# ICE.net
KiCad netlist of a schematic drawn in Altium Designer
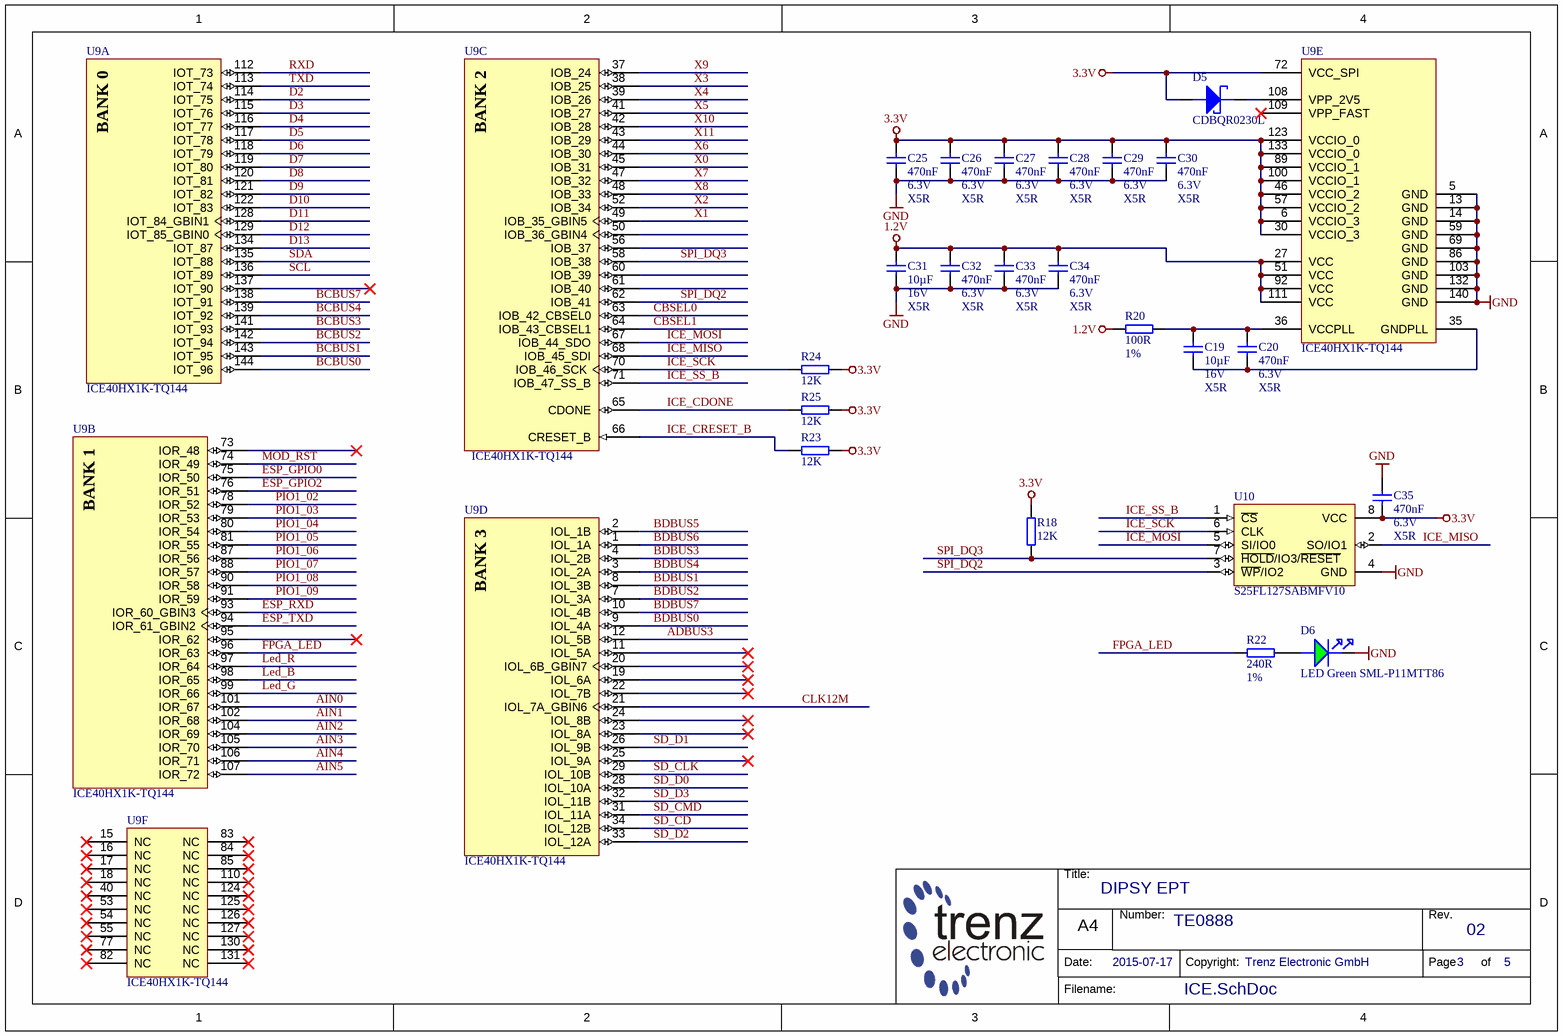
[diagram p0: ICE.SchDoc]

(export (version "E")
  (design (tool "Eeschema 10.0.6"))
  (components
    (comp (ref "C19")
      (value "10µF")
      (footprint "CAPC1608X90N")
      (description "KON 10µF 16V X5R SMD 20%")
      (fields
        (field (name "VOLTAGE") "16V")
        (field (name "TECHNOLOGY") "X5R")
        (field (name "TOLERANCE") "20%")
      )
      (libsource (lib "TE") (part "CAP-NP"))
    )
    (comp (ref "C20")
      (value "470nF")
      (footprint "CAPC0603X33N")
      (description "KON 470nF X5R 6.3V SMD 20%")
      (fields
        (field (name "VOLTAGE") "6.3V")
        (field (name "TECHNOLOGY") "X5R")
        (field (name "TOLERANCE") "20%")
      )
      (libsource (lib "TE") (part "CAP-NP"))
    )
    (comp (ref "C25")
      (value "470nF")
      (footprint "CAPC0603X33N")
      (description "KON 470nF X5R 6.3V SMD 20%")
      (fields
        (field (name "VOLTAGE") "6.3V")
        (field (name "TECHNOLOGY") "X5R")
        (field (name "TOLERANCE") "20%")
      )
      (libsource (lib "TE") (part "CAP-NP"))
    )
    (comp (ref "C26")
      (value "470nF")
      (footprint "CAPC0603X33N")
      (description "KON 470nF X5R 6.3V SMD 20%")
      (fields
        (field (name "VOLTAGE") "6.3V")
        (field (name "TECHNOLOGY") "X5R")
        (field (name "TOLERANCE") "20%")
      )
      (libsource (lib "TE") (part "CAP-NP"))
    )
    (comp (ref "C27")
      (value "470nF")
      (footprint "CAPC0603X33N")
      (description "KON 470nF X5R 6.3V SMD 20%")
      (fields
        (field (name "VOLTAGE") "6.3V")
        (field (name "TECHNOLOGY") "X5R")
        (field (name "TOLERANCE") "20%")
      )
      (libsource (lib "TE") (part "CAP-NP"))
    )
    (comp (ref "C28")
      (value "470nF")
      (footprint "CAPC0603X33N")
      (description "KON 470nF X5R 6.3V SMD 20%")
      (fields
        (field (name "VOLTAGE") "6.3V")
        (field (name "TECHNOLOGY") "X5R")
        (field (name "TOLERANCE") "20%")
      )
      (libsource (lib "TE") (part "CAP-NP"))
    )
    (comp (ref "C29")
      (value "470nF")
      (footprint "CAPC0603X33N")
      (description "KON 470nF X5R 6.3V SMD 20%")
      (fields
        (field (name "VOLTAGE") "6.3V")
        (field (name "TECHNOLOGY") "X5R")
        (field (name "TOLERANCE") "20%")
      )
      (libsource (lib "TE") (part "CAP-NP"))
    )
    (comp (ref "C30")
      (value "470nF")
      (footprint "CAPC0603X33N")
      (description "KON 470nF X5R 6.3V SMD 20%")
      (fields
        (field (name "VOLTAGE") "6.3V")
        (field (name "TECHNOLOGY") "X5R")
        (field (name "TOLERANCE") "20%")
      )
      (libsource (lib "TE") (part "CAP-NP"))
    )
    (comp (ref "C31")
      (value "10µF")
      (footprint "CAPC1608X90N")
      (description "KON 10µF 16V X5R SMD 20%")
      (fields
        (field (name "VOLTAGE") "16V")
        (field (name "TECHNOLOGY") "X5R")
        (field (name "TOLERANCE") "20%")
      )
      (libsource (lib "TE") (part "CAP-NP"))
    )
    (comp (ref "C32")
      (value "470nF")
      (footprint "CAPC0603X33N")
      (description "KON 470nF X5R 6.3V SMD 20%")
      (fields
        (field (name "VOLTAGE") "6.3V")
        (field (name "TECHNOLOGY") "X5R")
        (field (name "TOLERANCE") "20%")
      )
      (libsource (lib "TE") (part "CAP-NP"))
    )
    (comp (ref "C33")
      (value "470nF")
      (footprint "CAPC0603X33N")
      (description "KON 470nF X5R 6.3V SMD 20%")
      (fields
        (field (name "VOLTAGE") "6.3V")
        (field (name "TECHNOLOGY") "X5R")
        (field (name "TOLERANCE") "20%")
      )
      (libsource (lib "TE") (part "CAP-NP"))
    )
    (comp (ref "C34")
      (value "470nF")
      (footprint "CAPC0603X33N")
      (description "KON 470nF X5R 6.3V SMD 20%")
      (fields
        (field (name "VOLTAGE") "6.3V")
        (field (name "TECHNOLOGY") "X5R")
        (field (name "TOLERANCE") "20%")
      )
      (libsource (lib "TE") (part "CAP-NP"))
    )
    (comp (ref "C35")
      (value "470nF")
      (footprint "CAPC0603X33N")
      (description "KON 470nF X5R 6.3V SMD 20%")
      (fields
        (field (name "VOLTAGE") "6.3V")
        (field (name "TECHNOLOGY") "X5R")
        (field (name "TOLERANCE") "20%")
      )
      (libsource (lib "TE") (part "CAP-NP"))
    )
    (comp (ref "D5")
      (value "CDBQR0230L")
      (footprint "DIOC1006X55N")
      (fields (field (name "VOLTAGE") "0.2A"))
      (libsource (lib "TE") (part "SCHOTTKY"))
    )
    (comp (ref "D6")
      (value "LED Green SML-P11MTT86")
      (footprint "LEDC1006X25N_GREEN")
      (description "LED Grün SML-P11MTT86 SMD")
      (libsource (lib "TE") (part "LED_GRUEN"))
    )
    (comp (ref "R18")
      (value "12K")
      (footprint "RESC1005X40N")
      (description "WID SMD 12K 1% 0,063W")
      (libsource (lib "TE") (part "RES"))
    )
    (comp (ref "R20")
      (value "100R")
      (footprint "RESC1005X40N")
      (description "WID SMD 100R 1% 0,063W")
      (fields (field (name "TOLERANCE") "1%"))
      (libsource (lib "TE") (part "RES"))
    )
    (comp (ref "R22")
      (value "240R")
      (footprint "RESC1005X40N")
      (description "WID SMD 240R 1% 0,063W")
      (fields (field (name "TOLERANCE") "1%"))
      (libsource (lib "TE") (part "RES"))
    )
    (comp (ref "R23")
      (value "12K")
      (footprint "RESC1005X40N")
      (description "WID SMD 12K 1% 0,063W")
      (libsource (lib "TE") (part "RES"))
    )
    (comp (ref "R24")
      (value "12K")
      (footprint "RESC1005X40N")
      (description "WID SMD 12K 1% 0,063W")
      (libsource (lib "TE") (part "RES"))
    )
    (comp (ref "R25")
      (value "12K")
      (footprint "RESC1005X40N")
      (description "WID SMD 12K 1% 0,063W")
      (libsource (lib "TE") (part "RES"))
    )
    (comp (ref "U9")
      (value "ICE40HX1K-TQ144")
      (footprint "QFP50P2200X2200X160-144N")
      (libsource (lib "TE") (part "ICE40HX1K-TQ144"))
    )
    (comp (ref "U10")
      (value "S25FL127SABMFV10")
      (footprint "SOIC127P790X216-8N")
      (description "S25FL127SABMFV10 automotive SO8")
      (libsource (lib "TE") (part "S25FL127S-SO8"))
    )
  )
  (nets
    (net (code "1") (name "/ADBUS3") (class "Default")
      (node (ref "U9") (pin "12") (pinfunction "IOL_5B_12") (pintype "bidirectional"))
    )
    (net (code "2") (name "/AIN0") (class "Default")
      (node (ref "U9") (pin "101") (pinfunction "IOR_67_101") (pintype "bidirectional"))
    )
    (net (code "3") (name "/AIN1") (class "Default")
      (node (ref "U9") (pin "102") (pinfunction "IOR_68_102") (pintype "bidirectional"))
    )
    (net (code "4") (name "/AIN2") (class "Default")
      (node (ref "U9") (pin "104") (pinfunction "IOR_69_104") (pintype "bidirectional"))
    )
    (net (code "5") (name "/AIN3") (class "Default")
      (node (ref "U9") (pin "105") (pinfunction "IOR_70_105") (pintype "bidirectional"))
    )
    (net (code "6") (name "/AIN4") (class "Default")
      (node (ref "U9") (pin "106") (pinfunction "IOR_71_106") (pintype "bidirectional"))
    )
    (net (code "7") (name "/AIN5") (class "Default")
      (node (ref "U9") (pin "107") (pinfunction "IOR_72_107") (pintype "bidirectional"))
    )
    (net (code "8") (name "/BCBUS0") (class "Default")
      (node (ref "U9") (pin "144") (pinfunction "IOT_96_144") (pintype "bidirectional"))
    )
    (net (code "9") (name "/BCBUS1") (class "Default")
      (node (ref "U9") (pin "143") (pinfunction "IOT_95_143") (pintype "bidirectional"))
    )
    (net (code "10") (name "/BCBUS2") (class "Default")
      (node (ref "U9") (pin "142") (pinfunction "IOT_94_142") (pintype "bidirectional"))
    )
    (net (code "11") (name "/BCBUS3") (class "Default")
      (node (ref "U9") (pin "141") (pinfunction "IOT_93_141") (pintype "bidirectional"))
    )
    (net (code "12") (name "/BCBUS4") (class "Default")
      (node (ref "U9") (pin "139") (pinfunction "IOT_92_139") (pintype "bidirectional"))
    )
    (net (code "13") (name "/BCBUS7") (class "Default")
      (node (ref "U9") (pin "138") (pinfunction "IOT_91_138") (pintype "bidirectional"))
    )
    (net (code "14") (name "/BDBUS0") (class "Default")
      (node (ref "U9") (pin "9") (pinfunction "IOL_4A_9") (pintype "bidirectional"))
    )
    (net (code "15") (name "/BDBUS1") (class "Default")
      (node (ref "U9") (pin "8") (pinfunction "IOL_3B_8") (pintype "bidirectional"))
    )
    (net (code "16") (name "/BDBUS2") (class "Default")
      (node (ref "U9") (pin "7") (pinfunction "IOL_3A_7") (pintype "bidirectional"))
    )
    (net (code "17") (name "/BDBUS3") (class "Default")
      (node (ref "U9") (pin "4") (pinfunction "IOL_2B_4") (pintype "bidirectional"))
    )
    (net (code "18") (name "/BDBUS4") (class "Default")
      (node (ref "U9") (pin "3") (pinfunction "IOL_2A_3") (pintype "bidirectional"))
    )
    (net (code "19") (name "/BDBUS5") (class "Default")
      (node (ref "U9") (pin "2") (pinfunction "IOL_1B_2") (pintype "bidirectional"))
    )
    (net (code "20") (name "/BDBUS6") (class "Default")
      (node (ref "U9") (pin "1") (pinfunction "IOL_1A_1") (pintype "bidirectional"))
    )
    (net (code "21") (name "/BDBUS7") (class "Default")
      (node (ref "U9") (pin "10") (pinfunction "IOL_4B_10") (pintype "bidirectional"))
    )
    (net (code "22") (name "/CBSEL0") (class "Default")
      (node (ref "U9") (pin "63") (pinfunction "IOB_42_CBSEL0_63") (pintype "bidirectional"))
    )
    (net (code "23") (name "/CBSEL1") (class "Default")
      (node (ref "U9") (pin "64") (pinfunction "IOB_43_CBSEL1_64") (pintype "bidirectional"))
    )
    (net (code "24") (name "/CLK12M") (class "Default")
      (node (ref "U9") (pin "21") (pinfunction "IOL_7A_GBIN6_21") (pintype "bidirectional"))
    )
    (net (code "25") (name "/D2") (class "Default")
      (node (ref "U9") (pin "114") (pinfunction "IOT_75_114") (pintype "bidirectional"))
    )
    (net (code "26") (name "/D3") (class "Default")
      (node (ref "U9") (pin "115") (pinfunction "IOT_76_115") (pintype "bidirectional"))
    )
    (net (code "27") (name "/D4") (class "Default")
      (node (ref "U9") (pin "116") (pinfunction "IOT_77_116") (pintype "bidirectional"))
    )
    (net (code "28") (name "/D5") (class "Default")
      (node (ref "U9") (pin "117") (pinfunction "IOT_78_117") (pintype "bidirectional"))
    )
    (net (code "29") (name "/D6") (class "Default")
      (node (ref "U9") (pin "118") (pinfunction "IOT_79_118") (pintype "bidirectional"))
    )
    (net (code "30") (name "/D7") (class "Default")
      (node (ref "U9") (pin "119") (pinfunction "IOT_80_119") (pintype "bidirectional"))
    )
    (net (code "31") (name "/D8") (class "Default")
      (node (ref "U9") (pin "120") (pinfunction "IOT_81_120") (pintype "bidirectional"))
    )
    (net (code "32") (name "/D9") (class "Default")
      (node (ref "U9") (pin "121") (pinfunction "IOT_82_121") (pintype "bidirectional"))
    )
    (net (code "33") (name "/D10") (class "Default")
      (node (ref "U9") (pin "122") (pinfunction "IOT_83_122") (pintype "bidirectional"))
    )
    (net (code "34") (name "/D11") (class "Default")
      (node (ref "U9") (pin "128") (pinfunction "IOT_84_GBIN1_128") (pintype "bidirectional"))
    )
    (net (code "35") (name "/D12") (class "Default")
      (node (ref "U9") (pin "129") (pinfunction "IOT_85_GBIN0_129") (pintype "bidirectional"))
    )
    (net (code "36") (name "/D13") (class "Default")
      (node (ref "U9") (pin "134") (pinfunction "IOT_87_134") (pintype "bidirectional"))
    )
    (net (code "37") (name "/ESP_GPIO0") (class "Default")
      (node (ref "U9") (pin "75") (pinfunction "IOR_50_75") (pintype "bidirectional"))
    )
    (net (code "38") (name "/ESP_GPIO2") (class "Default")
      (node (ref "U9") (pin "76") (pinfunction "IOR_51_76") (pintype "bidirectional"))
    )
    (net (code "39") (name "/ESP_RXD") (class "Default")
      (node (ref "U9") (pin "93") (pinfunction "IOR_60_GBIN3_93") (pintype "bidirectional"))
    )
    (net (code "40") (name "/ESP_TXD") (class "Default")
      (node (ref "U9") (pin "94") (pinfunction "IOR_61_GBIN2_94") (pintype "bidirectional"))
    )
    (net (code "41") (name "/FPGA_LED") (class "Default")
      (node (ref "R22") (pin "2") (pinfunction "2_2") (pintype "passive"))
      (node (ref "U9") (pin "96") (pinfunction "IOR_63_96") (pintype "bidirectional"))
    )
    (net (code "42") (name "/ICE_CDONE") (class "Default")
      (node (ref "R25") (pin "2") (pinfunction "2_2") (pintype "passive"))
      (node (ref "U9") (pin "65") (pinfunction "CDONE_65") (pintype "bidirectional"))
    )
    (net (code "43") (name "/ICE_CRESET_B") (class "Default")
      (node (ref "R23") (pin "2") (pinfunction "2_2") (pintype "passive"))
      (node (ref "U9") (pin "66") (pinfunction "CRESET_B_66") (pintype "input"))
    )
    (net (code "44") (name "/ICE_MISO") (class "Default")
      (node (ref "U10") (pin "2") (pinfunction "SO/IO1_2") (pintype "bidirectional"))
      (node (ref "U9") (pin "68") (pinfunction "IOB_45_SDI_68") (pintype "bidirectional"))
    )
    (net (code "45") (name "/ICE_MOSI") (class "Default")
      (node (ref "U10") (pin "5") (pinfunction "SI/IO0_5") (pintype "bidirectional"))
      (node (ref "U9") (pin "67") (pinfunction "IOB_44_SDO_67") (pintype "bidirectional"))
    )
    (net (code "46") (name "/ICE_SCK") (class "Default")
      (node (ref "R24") (pin "2") (pinfunction "2_2") (pintype "passive"))
      (node (ref "U10") (pin "6") (pinfunction "CLK_6") (pintype "input"))
      (node (ref "U9") (pin "70") (pinfunction "IOB_46_SCK_70") (pintype "bidirectional"))
    )
    (net (code "47") (name "/ICE_SS_B") (class "Default")
      (node (ref "U10") (pin "1") (pinfunction "~{CS}_1") (pintype "input"))
      (node (ref "U9") (pin "71") (pinfunction "IOB_47_SS_B_71") (pintype "bidirectional"))
    )
    (net (code "48") (name "/Led_B") (class "Default")
      (node (ref "U9") (pin "98") (pinfunction "IOR_65_98") (pintype "bidirectional"))
    )
    (net (code "49") (name "/Led_G") (class "Default")
      (node (ref "U9") (pin "99") (pinfunction "IOR_66_99") (pintype "bidirectional"))
    )
    (net (code "50") (name "/Led_R") (class "Default")
      (node (ref "U9") (pin "97") (pinfunction "IOR_64_97") (pintype "bidirectional"))
    )
    (net (code "51") (name "/MOD_RST") (class "Default")
      (node (ref "U9") (pin "74") (pinfunction "IOR_49_74") (pintype "bidirectional"))
    )
    (net (code "52") (name "/PIO1_02") (class "Default")
      (node (ref "U9") (pin "78") (pinfunction "IOR_52_78") (pintype "bidirectional"))
    )
    (net (code "53") (name "/PIO1_03") (class "Default")
      (node (ref "U9") (pin "79") (pinfunction "IOR_53_79") (pintype "bidirectional"))
    )
    (net (code "54") (name "/PIO1_04") (class "Default")
      (node (ref "U9") (pin "80") (pinfunction "IOR_54_80") (pintype "bidirectional"))
    )
    (net (code "55") (name "/PIO1_05") (class "Default")
      (node (ref "U9") (pin "81") (pinfunction "IOR_55_81") (pintype "bidirectional"))
    )
    (net (code "56") (name "/PIO1_06") (class "Default")
      (node (ref "U9") (pin "87") (pinfunction "IOR_56_87") (pintype "bidirectional"))
    )
    (net (code "57") (name "/PIO1_07") (class "Default")
      (node (ref "U9") (pin "88") (pinfunction "IOR_57_88") (pintype "bidirectional"))
    )
    (net (code "58") (name "/PIO1_08") (class "Default")
      (node (ref "U9") (pin "90") (pinfunction "IOR_58_90") (pintype "bidirectional"))
    )
    (net (code "59") (name "/PIO1_09") (class "Default")
      (node (ref "U9") (pin "91") (pinfunction "IOR_59_91") (pintype "bidirectional"))
    )
    (net (code "60") (name "/RXD") (class "Default")
      (node (ref "U9") (pin "112") (pinfunction "IOT_73_112") (pintype "bidirectional"))
    )
    (net (code "61") (name "/SCL") (class "Default")
      (node (ref "U9") (pin "136") (pinfunction "IOT_89_136") (pintype "bidirectional"))
    )
    (net (code "62") (name "/SDA") (class "Default")
      (node (ref "U9") (pin "135") (pinfunction "IOT_88_135") (pintype "bidirectional"))
    )
    (net (code "63") (name "/SD_CD") (class "Default")
      (node (ref "U9") (pin "34") (pinfunction "IOL_12B_34") (pintype "bidirectional"))
    )
    (net (code "64") (name "/SD_CLK") (class "Default")
      (node (ref "U9") (pin "29") (pinfunction "IOL_10B_29") (pintype "bidirectional"))
    )
    (net (code "65") (name "/SD_CMD") (class "Default")
      (node (ref "U9") (pin "31") (pinfunction "IOL_11A_31") (pintype "bidirectional"))
    )
    (net (code "66") (name "/SD_D0") (class "Default")
      (node (ref "U9") (pin "28") (pinfunction "IOL_10A_28") (pintype "bidirectional"))
    )
    (net (code "67") (name "/SD_D1") (class "Default")
      (node (ref "U9") (pin "26") (pinfunction "IOL_9B_26") (pintype "bidirectional"))
    )
    (net (code "68") (name "/SD_D2") (class "Default")
      (node (ref "U9") (pin "33") (pinfunction "IOL_12A_33") (pintype "bidirectional"))
    )
    (net (code "69") (name "/SD_D3") (class "Default")
      (node (ref "U9") (pin "32") (pinfunction "IOL_11B_32") (pintype "bidirectional"))
    )
    (net (code "70") (name "/SPI_DQ2") (class "Default")
      (node (ref "U10") (pin "3") (pinfunction "~{WP}/IO2_3") (pintype "bidirectional"))
      (node (ref "U9") (pin "62") (pinfunction "IOB_41_62") (pintype "bidirectional"))
    )
    (net (code "71") (name "/SPI_DQ3") (class "Default")
      (node (ref "R18") (pin "2") (pinfunction "2_2") (pintype "passive"))
      (node (ref "U10") (pin "7") (pinfunction "~{HOLD}/IO3/~{RESET}_7") (pintype "bidirectional"))
      (node (ref "U9") (pin "58") (pinfunction "IOB_38_58") (pintype "bidirectional"))
    )
    (net (code "72") (name "/TXD") (class "Default")
      (node (ref "U9") (pin "113") (pinfunction "IOT_74_113") (pintype "bidirectional"))
    )
    (net (code "73") (name "/X0") (class "Default")
      (node (ref "U9") (pin "45") (pinfunction "IOB_31_45") (pintype "bidirectional"))
    )
    (net (code "74") (name "/X1") (class "Default")
      (node (ref "U9") (pin "49") (pinfunction "IOB_35_GBIN5_49") (pintype "bidirectional"))
    )
    (net (code "75") (name "/X2") (class "Default")
      (node (ref "U9") (pin "52") (pinfunction "IOB_34_52") (pintype "bidirectional"))
    )
    (net (code "76") (name "/X3") (class "Default")
      (node (ref "U9") (pin "38") (pinfunction "IOB_25_38") (pintype "bidirectional"))
    )
    (net (code "77") (name "/X4") (class "Default")
      (node (ref "U9") (pin "39") (pinfunction "IOB_26_39") (pintype "bidirectional"))
    )
    (net (code "78") (name "/X5") (class "Default")
      (node (ref "U9") (pin "41") (pinfunction "IOB_27_41") (pintype "bidirectional"))
    )
    (net (code "79") (name "/X6") (class "Default")
      (node (ref "U9") (pin "44") (pinfunction "IOB_30_44") (pintype "bidirectional"))
    )
    (net (code "80") (name "/X7") (class "Default")
      (node (ref "U9") (pin "47") (pinfunction "IOB_32_47") (pintype "bidirectional"))
    )
    (net (code "81") (name "/X8") (class "Default")
      (node (ref "U9") (pin "48") (pinfunction "IOB_33_48") (pintype "bidirectional"))
    )
    (net (code "82") (name "/X9") (class "Default")
      (node (ref "U9") (pin "37") (pinfunction "IOB_24_37") (pintype "bidirectional"))
    )
    (net (code "83") (name "/X10") (class "Default")
      (node (ref "U9") (pin "42") (pinfunction "IOB_28_42") (pintype "bidirectional"))
    )
    (net (code "84") (name "/X11") (class "Default")
      (node (ref "U9") (pin "43") (pinfunction "IOB_29_43") (pintype "bidirectional"))
    )
    (net (code "85") (name "1.2V") (class "Default")
      (node (ref "C31") (pin "1") (pinfunction "1_1") (pintype "passive"))
      (node (ref "C32") (pin "2") (pinfunction "2_2") (pintype "passive"))
      (node (ref "C33") (pin "2") (pinfunction "2_2") (pintype "passive"))
      (node (ref "C34") (pin "2") (pinfunction "2_2") (pintype "passive"))
      (node (ref "R20") (pin "1") (pinfunction "1_1") (pintype "passive"))
      (node (ref "U9") (pin "111") (pinfunction "VCC_111") (pintype "power_in"))
      (node (ref "U9") (pin "27") (pinfunction "VCC_27") (pintype "power_in"))
      (node (ref "U9") (pin "51") (pinfunction "VCC_51") (pintype "power_in"))
      (node (ref "U9") (pin "92") (pinfunction "VCC_92") (pintype "power_in"))
    )
    (net (code "86") (name "3.3V") (class "Default")
      (node (ref "C25") (pin "2") (pinfunction "2_2") (pintype "passive"))
      (node (ref "C26") (pin "2") (pinfunction "2_2") (pintype "passive"))
      (node (ref "C27") (pin "2") (pinfunction "2_2") (pintype "passive"))
      (node (ref "C28") (pin "2") (pinfunction "2_2") (pintype "passive"))
      (node (ref "C29") (pin "2") (pinfunction "2_2") (pintype "passive"))
      (node (ref "C30") (pin "2") (pinfunction "2_2") (pintype "passive"))
      (node (ref "C35") (pin "1") (pinfunction "1_1") (pintype "passive"))
      (node (ref "D5") (pin "2") (pinfunction "ANODE_2") (pintype "passive"))
      (node (ref "R18") (pin "1") (pinfunction "1_1") (pintype "passive"))
      (node (ref "R23") (pin "1") (pinfunction "1_1") (pintype "passive"))
      (node (ref "R24") (pin "1") (pinfunction "1_1") (pintype "passive"))
      (node (ref "R25") (pin "1") (pinfunction "1_1") (pintype "passive"))
      (node (ref "U10") (pin "8") (pinfunction "VCC_8") (pintype "power_in"))
      (node (ref "U9") (pin "100") (pinfunction "VCCIO_1_100") (pintype "power_in"))
      (node (ref "U9") (pin "123") (pinfunction "VCCIO_0_123") (pintype "power_in"))
      (node (ref "U9") (pin "133") (pinfunction "VCCIO_0_133") (pintype "power_in"))
      (node (ref "U9") (pin "30") (pinfunction "VCCIO_3_30") (pintype "power_in"))
      (node (ref "U9") (pin "46") (pinfunction "VCCIO_2_46") (pintype "power_in"))
      (node (ref "U9") (pin "57") (pinfunction "VCCIO_2_57") (pintype "power_in"))
      (node (ref "U9") (pin "6") (pinfunction "VCCIO_3_6") (pintype "power_in"))
      (node (ref "U9") (pin "72") (pinfunction "VCC_SPI_72") (pintype "power_in"))
      (node (ref "U9") (pin "89") (pinfunction "VCCIO_1_89") (pintype "power_in"))
    )
    (net (code "87") (name "GND") (class "Default")
      (node (ref "C25") (pin "1") (pinfunction "1_1") (pintype "passive"))
      (node (ref "C26") (pin "1") (pinfunction "1_1") (pintype "passive"))
      (node (ref "C27") (pin "1") (pinfunction "1_1") (pintype "passive"))
      (node (ref "C28") (pin "1") (pinfunction "1_1") (pintype "passive"))
      (node (ref "C29") (pin "1") (pinfunction "1_1") (pintype "passive"))
      (node (ref "C30") (pin "1") (pinfunction "1_1") (pintype "passive"))
      (node (ref "C31") (pin "2") (pinfunction "2_2") (pintype "passive"))
      (node (ref "C32") (pin "1") (pinfunction "1_1") (pintype "passive"))
      (node (ref "C33") (pin "1") (pinfunction "1_1") (pintype "passive"))
      (node (ref "C34") (pin "1") (pinfunction "1_1") (pintype "passive"))
      (node (ref "C35") (pin "2") (pinfunction "2_2") (pintype "passive"))
      (node (ref "D6") (pin "K") (pinfunction "K_K") (pintype "passive"))
      (node (ref "U10") (pin "4") (pinfunction "GND_4") (pintype "power_in"))
      (node (ref "U9") (pin "103") (pinfunction "GND_103") (pintype "power_in"))
      (node (ref "U9") (pin "13") (pinfunction "GND_13") (pintype "power_in"))
      (node (ref "U9") (pin "132") (pinfunction "GND_132") (pintype "power_in"))
      (node (ref "U9") (pin "14") (pinfunction "GND_14") (pintype "power_in"))
      (node (ref "U9") (pin "140") (pinfunction "GND_140") (pintype "power_in"))
      (node (ref "U9") (pin "5") (pinfunction "GND_5") (pintype "power_in"))
      (node (ref "U9") (pin "59") (pinfunction "GND_59") (pintype "power_in"))
      (node (ref "U9") (pin "69") (pinfunction "GND_69") (pintype "power_in"))
      (node (ref "U9") (pin "86") (pinfunction "GND_86") (pintype "power_in"))
    )
    (net (code "88") (name "Net-(D5-KATHODE)") (class "Default")
      (node (ref "D5") (pin "1") (pinfunction "KATHODE_1") (pintype "passive"))
      (node (ref "U9") (pin "108") (pinfunction "VPP_2V5_108") (pintype "power_in"))
    )
    (net (code "89") (name "Net-(D6-PadA)") (class "Default")
      (node (ref "D6") (pin "A") (pinfunction "A_A") (pintype "passive"))
      (node (ref "R22") (pin "1") (pinfunction "1_1") (pintype "passive"))
    )
    (net (code "90") (name "Net-(U9E-GNDPLL)") (class "Default")
      (node (ref "C19") (pin "2") (pinfunction "2_2") (pintype "passive"))
      (node (ref "C20") (pin "1") (pinfunction "1_1") (pintype "passive"))
      (node (ref "U9") (pin "35") (pinfunction "GNDPLL_35") (pintype "power_in"))
    )
    (net (code "91") (name "Net-(U9E-VCCPLL)") (class "Default")
      (node (ref "C19") (pin "1") (pinfunction "1_1") (pintype "passive"))
      (node (ref "C20") (pin "2") (pinfunction "2_2") (pintype "passive"))
      (node (ref "R20") (pin "2") (pinfunction "2_2") (pintype "passive"))
      (node (ref "U9") (pin "36") (pinfunction "VCCPLL_36") (pintype "power_in"))
    )
    (net (code "92") (name "unconnected-(U9A-IOT_90-Pad137)") (class "Default")
      (node (ref "U9") (pin "137") (pinfunction "IOT_90_137") (pintype "bidirectional+no_connect"))
    )
    (net (code "93") (name "unconnected-(U9B-IOR_48-Pad73)") (class "Default")
      (node (ref "U9") (pin "73") (pinfunction "IOR_48_73") (pintype "bidirectional+no_connect"))
    )
    (net (code "94") (name "unconnected-(U9B-IOR_62-Pad95)") (class "Default")
      (node (ref "U9") (pin "95") (pinfunction "IOR_62_95") (pintype "bidirectional+no_connect"))
    )
    (net (code "95") (name "unconnected-(U9C-IOB_36_GBIN4-Pad50)") (class "Default")
      (node (ref "U9") (pin "50") (pinfunction "IOB_36_GBIN4_50") (pintype "bidirectional"))
    )
    (net (code "96") (name "unconnected-(U9C-IOB_37-Pad56)") (class "Default")
      (node (ref "U9") (pin "56") (pinfunction "IOB_37_56") (pintype "bidirectional"))
    )
    (net (code "97") (name "unconnected-(U9C-IOB_39-Pad60)") (class "Default")
      (node (ref "U9") (pin "60") (pinfunction "IOB_39_60") (pintype "bidirectional"))
    )
    (net (code "98") (name "unconnected-(U9C-IOB_40-Pad61)") (class "Default")
      (node (ref "U9") (pin "61") (pinfunction "IOB_40_61") (pintype "bidirectional"))
    )
    (net (code "99") (name "unconnected-(U9D-IOL_5A-Pad11)") (class "Default")
      (node (ref "U9") (pin "11") (pinfunction "IOL_5A_11") (pintype "bidirectional+no_connect"))
    )
    (net (code "100") (name "unconnected-(U9D-IOL_6A-Pad19)") (class "Default")
      (node (ref "U9") (pin "19") (pinfunction "IOL_6A_19") (pintype "bidirectional+no_connect"))
    )
    (net (code "101") (name "unconnected-(U9D-IOL_6B_GBIN7-Pad20)") (class "Default")
      (node (ref "U9") (pin "20") (pinfunction "IOL_6B_GBIN7_20") (pintype "bidirectional+no_connect"))
    )
    (net (code "102") (name "unconnected-(U9D-IOL_7B-Pad22)") (class "Default")
      (node (ref "U9") (pin "22") (pinfunction "IOL_7B_22") (pintype "bidirectional+no_connect"))
    )
    (net (code "103") (name "unconnected-(U9D-IOL_8A-Pad23)") (class "Default")
      (node (ref "U9") (pin "23") (pinfunction "IOL_8A_23") (pintype "bidirectional+no_connect"))
    )
    (net (code "104") (name "unconnected-(U9D-IOL_8B-Pad24)") (class "Default")
      (node (ref "U9") (pin "24") (pinfunction "IOL_8B_24") (pintype "bidirectional+no_connect"))
    )
    (net (code "105") (name "unconnected-(U9D-IOL_9A-Pad25)") (class "Default")
      (node (ref "U9") (pin "25") (pinfunction "IOL_9A_25") (pintype "bidirectional+no_connect"))
    )
    (net (code "106") (name "unconnected-(U9E-VPP_FAST-Pad109)") (class "Default")
      (node (ref "U9") (pin "109") (pinfunction "VPP_FAST_109") (pintype "power_in+no_connect"))
    )
    (net (code "107") (name "unconnected-(U9F-NC-Pad15)") (class "Default")
      (node (ref "U9") (pin "15") (pinfunction "NC_15") (pintype "passive+no_connect"))
    )
    (net (code "108") (name "unconnected-(U9F-NC-Pad16)") (class "Default")
      (node (ref "U9") (pin "16") (pinfunction "NC_16") (pintype "passive+no_connect"))
    )
    (net (code "109") (name "unconnected-(U9F-NC-Pad17)") (class "Default")
      (node (ref "U9") (pin "17") (pinfunction "NC_17") (pintype "passive+no_connect"))
    )
    (net (code "110") (name "unconnected-(U9F-NC-Pad18)") (class "Default")
      (node (ref "U9") (pin "18") (pinfunction "NC_18") (pintype "passive+no_connect"))
    )
    (net (code "111") (name "unconnected-(U9F-NC-Pad40)") (class "Default")
      (node (ref "U9") (pin "40") (pinfunction "NC_40") (pintype "passive+no_connect"))
    )
    (net (code "112") (name "unconnected-(U9F-NC-Pad53)") (class "Default")
      (node (ref "U9") (pin "53") (pinfunction "NC_53") (pintype "passive+no_connect"))
    )
    (net (code "113") (name "unconnected-(U9F-NC-Pad54)") (class "Default")
      (node (ref "U9") (pin "54") (pinfunction "NC_54") (pintype "passive+no_connect"))
    )
    (net (code "114") (name "unconnected-(U9F-NC-Pad55)") (class "Default")
      (node (ref "U9") (pin "55") (pinfunction "NC_55") (pintype "passive+no_connect"))
    )
    (net (code "115") (name "unconnected-(U9F-NC-Pad77)") (class "Default")
      (node (ref "U9") (pin "77") (pinfunction "NC_77") (pintype "passive+no_connect"))
    )
    (net (code "116") (name "unconnected-(U9F-NC-Pad82)") (class "Default")
      (node (ref "U9") (pin "82") (pinfunction "NC_82") (pintype "passive+no_connect"))
    )
    (net (code "117") (name "unconnected-(U9F-NC-Pad83)") (class "Default")
      (node (ref "U9") (pin "83") (pinfunction "NC_83") (pintype "passive+no_connect"))
    )
    (net (code "118") (name "unconnected-(U9F-NC-Pad84)") (class "Default")
      (node (ref "U9") (pin "84") (pinfunction "NC_84") (pintype "passive+no_connect"))
    )
    (net (code "119") (name "unconnected-(U9F-NC-Pad85)") (class "Default")
      (node (ref "U9") (pin "85") (pinfunction "NC_85") (pintype "passive+no_connect"))
    )
    (net (code "120") (name "unconnected-(U9F-NC-Pad110)") (class "Default")
      (node (ref "U9") (pin "110") (pinfunction "NC_110") (pintype "passive+no_connect"))
    )
    (net (code "121") (name "unconnected-(U9F-NC-Pad124)") (class "Default")
      (node (ref "U9") (pin "124") (pinfunction "NC_124") (pintype "passive+no_connect"))
    )
    (net (code "122") (name "unconnected-(U9F-NC-Pad125)") (class "Default")
      (node (ref "U9") (pin "125") (pinfunction "NC_125") (pintype "passive+no_connect"))
    )
    (net (code "123") (name "unconnected-(U9F-NC-Pad126)") (class "Default")
      (node (ref "U9") (pin "126") (pinfunction "NC_126") (pintype "passive+no_connect"))
    )
    (net (code "124") (name "unconnected-(U9F-NC-Pad127)") (class "Default")
      (node (ref "U9") (pin "127") (pinfunction "NC_127") (pintype "passive+no_connect"))
    )
    (net (code "125") (name "unconnected-(U9F-NC-Pad130)") (class "Default")
      (node (ref "U9") (pin "130") (pinfunction "NC_130") (pintype "passive+no_connect"))
    )
    (net (code "126") (name "unconnected-(U9F-NC-Pad131)") (class "Default")
      (node (ref "U9") (pin "131") (pinfunction "NC_131") (pintype "passive+no_connect"))
    )
  )
)
